# TPA3116D2.net
KiCad netlist of a schematic drawn in Altium Designer
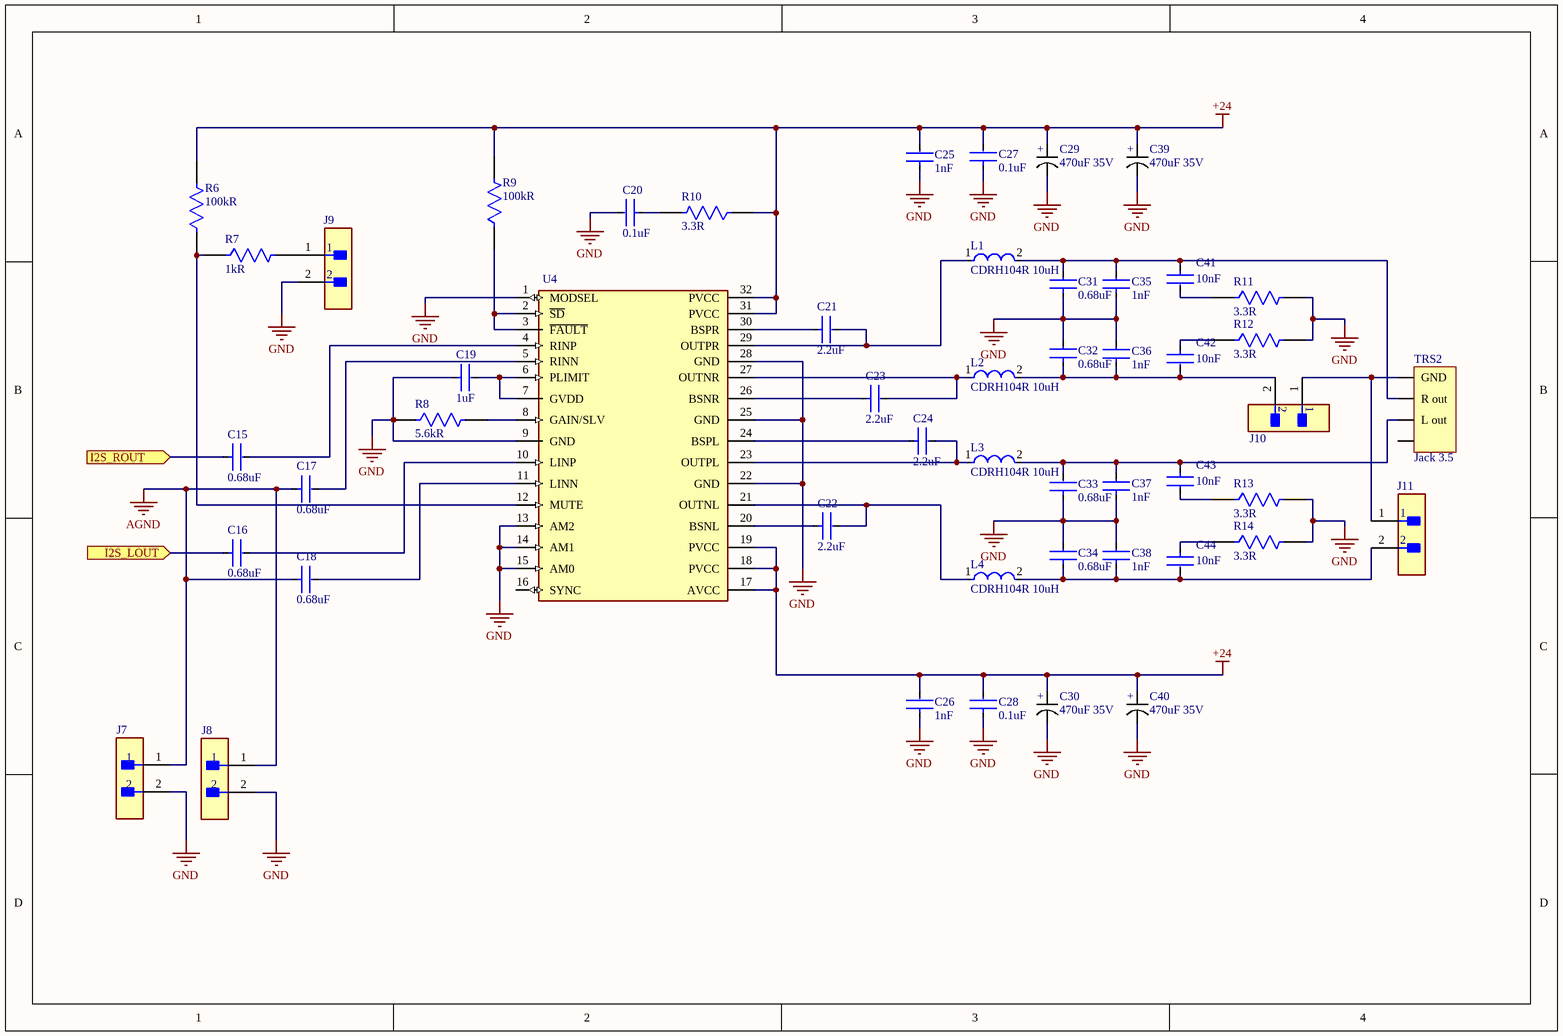
[diagram p0: TPA3116D2.SchDoc]

(export (version "E")
  (design (tool "Eeschema 10.0.6"))
  (components
    (comp (ref "C15")
      (value "0.68uF")
      (footprint "FP-CL21-IPC_C")
      (description "CL21 Series 0805 47nF 50V ±5% Tolerance X7R Multilayer Ceramic Chip Capacitor")
      (fields (field (name "TOLERANCE") "5%"))
      (libsource (lib "Altium Content Vault") (part "b4654b650e69147ec39a6b967a45e02"))
    )
    (comp (ref "C16")
      (value "0.68uF")
      (footprint "FP-CL21-IPC_C")
      (description "CL21 Series 0805 47nF 50V ±5% Tolerance X7R Multilayer Ceramic Chip Capacitor")
      (fields (field (name "TOLERANCE") "5%"))
      (libsource (lib "Altium Content Vault") (part "b4654b650e69147ec39a6b967a45e02"))
    )
    (comp (ref "C17")
      (value "0.68uF")
      (footprint "FP-CL21-IPC_C")
      (description "CL21 Series 0805 47nF 50V ±5% Tolerance X7R Multilayer Ceramic Chip Capacitor")
      (fields (field (name "TOLERANCE") "5%"))
      (libsource (lib "Altium Content Vault") (part "b4654b650e69147ec39a6b967a45e02"))
    )
    (comp (ref "C18")
      (value "0.68uF")
      (footprint "FP-CL21-IPC_C")
      (description "CL21 Series 0805 47nF 50V ±5% Tolerance X7R Multilayer Ceramic Chip Capacitor")
      (fields (field (name "TOLERANCE") "5%"))
      (libsource (lib "Altium Content Vault") (part "b4654b650e69147ec39a6b967a45e02"))
    )
    (comp (ref "C19")
      (value "1uF")
      (footprint "FP-CL21-IPC_C")
      (description "CL21 Series 0805 47nF 50V ±5% Tolerance X7R Multilayer Ceramic Chip Capacitor")
      (fields (field (name "TOLERANCE") "5%"))
      (libsource (lib "Altium Content Vault") (part "b4654b650e69147ec39a6b967a45e02"))
    )
    (comp (ref "C20")
      (value "0.1uF")
      (footprint "FP-CL21-IPC_C")
      (description "CL21 Series 0805 47nF 50V ±5% Tolerance X7R Multilayer Ceramic Chip Capacitor")
      (fields (field (name "TOLERANCE") "5%"))
      (libsource (lib "Altium Content Vault") (part "b4654b650e69147ec39a6b967a45e02"))
    )
    (comp (ref "C21")
      (value "2.2uF")
      (footprint "FP-CL21-IPC_C")
      (description "CL21 Series 0805 47nF 50V ±5% Tolerance X7R Multilayer Ceramic Chip Capacitor")
      (fields (field (name "TOLERANCE") "5%"))
      (libsource (lib "Altium Content Vault") (part "b4654b650e69147ec39a6b967a45e02"))
    )
    (comp (ref "C22")
      (value "2.2uF")
      (footprint "FP-CL21-IPC_C")
      (description "CL21 Series 0805 47nF 50V ±5% Tolerance X7R Multilayer Ceramic Chip Capacitor")
      (fields (field (name "TOLERANCE") "5%"))
      (libsource (lib "Altium Content Vault") (part "b4654b650e69147ec39a6b967a45e02"))
    )
    (comp (ref "C23")
      (value "2.2uF")
      (footprint "FP-CL21-IPC_C")
      (description "CL21 Series 0805 47nF 50V ±5% Tolerance X7R Multilayer Ceramic Chip Capacitor")
      (fields (field (name "TOLERANCE") "5%"))
      (libsource (lib "Altium Content Vault") (part "b4654b650e69147ec39a6b967a45e02"))
    )
    (comp (ref "C24")
      (value "2.2uF")
      (footprint "FP-CL21-IPC_C")
      (description "CL21 Series 0805 47nF 50V ±5% Tolerance X7R Multilayer Ceramic Chip Capacitor")
      (fields (field (name "TOLERANCE") "5%"))
      (libsource (lib "Altium Content Vault") (part "b4654b650e69147ec39a6b967a45e02"))
    )
    (comp (ref "C25")
      (value "1nF")
      (footprint "FP-CL21-IPC_C")
      (description "CL21 Series 0805 47nF 50V ±5% Tolerance X7R Multilayer Ceramic Chip Capacitor")
      (fields (field (name "TOLERANCE") "5%"))
      (libsource (lib "Altium Content Vault") (part "b4654b650e69147ec39a6b967a45e02"))
    )
    (comp (ref "C26")
      (value "1nF")
      (footprint "FP-CL21-IPC_C")
      (description "CL21 Series 0805 47nF 50V ±5% Tolerance X7R Multilayer Ceramic Chip Capacitor")
      (fields (field (name "TOLERANCE") "5%"))
      (libsource (lib "Altium Content Vault") (part "b4654b650e69147ec39a6b967a45e02"))
    )
    (comp (ref "C27")
      (value "0.1uF")
      (footprint "FP-CL21-IPC_C")
      (description "CL21 Series 0805 47nF 50V ±5% Tolerance X7R Multilayer Ceramic Chip Capacitor")
      (fields (field (name "TOLERANCE") "5%"))
      (libsource (lib "Altium Content Vault") (part "b4654b650e69147ec39a6b967a45e02"))
    )
    (comp (ref "C28")
      (value "0.1uF")
      (footprint "FP-CL21-IPC_C")
      (description "CL21 Series 0805 47nF 50V ±5% Tolerance X7R Multilayer Ceramic Chip Capacitor")
      (fields (field (name "TOLERANCE") "5%"))
      (libsource (lib "Altium Content Vault") (part "b4654b650e69147ec39a6b967a45e02"))
    )
    (comp (ref "C29")
      (value "470uF 35V")
      (footprint "CAP VT 470uF 35V")
      (libsource (lib "Schemati_design") (part "Cap{colon} VT 470uF 35V"))
    )
    (comp (ref "C30")
      (value "470uF 35V")
      (footprint "CAP VT 470uF 35V")
      (libsource (lib "Schemati_design") (part "Cap{colon} VT 470uF 35V"))
    )
    (comp (ref "C31")
      (value "0.68uF")
      (footprint "FP-CL21-IPC_C")
      (description "CL21 Series 0805 47nF 50V ±5% Tolerance X7R Multilayer Ceramic Chip Capacitor")
      (fields (field (name "TOLERANCE") "5%"))
      (libsource (lib "Altium Content Vault") (part "b4654b650e69147ec39a6b967a45e02"))
    )
    (comp (ref "C32")
      (value "0.68uF")
      (footprint "FP-CL21-IPC_C")
      (description "CL21 Series 0805 47nF 50V ±5% Tolerance X7R Multilayer Ceramic Chip Capacitor")
      (fields (field (name "TOLERANCE") "5%"))
      (libsource (lib "Altium Content Vault") (part "b4654b650e69147ec39a6b967a45e02"))
    )
    (comp (ref "C33")
      (value "0.68uF")
      (footprint "FP-CL21-IPC_C")
      (description "CL21 Series 0805 47nF 50V ±5% Tolerance X7R Multilayer Ceramic Chip Capacitor")
      (fields (field (name "TOLERANCE") "5%"))
      (libsource (lib "Altium Content Vault") (part "b4654b650e69147ec39a6b967a45e02"))
    )
    (comp (ref "C34")
      (value "0.68uF")
      (footprint "FP-CL21-IPC_C")
      (description "CL21 Series 0805 47nF 50V ±5% Tolerance X7R Multilayer Ceramic Chip Capacitor")
      (fields (field (name "TOLERANCE") "5%"))
      (libsource (lib "Altium Content Vault") (part "b4654b650e69147ec39a6b967a45e02"))
    )
    (comp (ref "C35")
      (value "1nF")
      (footprint "FP-CL21-IPC_C")
      (description "CL21 Series 0805 47nF 50V ±5% Tolerance X7R Multilayer Ceramic Chip Capacitor")
      (fields (field (name "TOLERANCE") "5%"))
      (libsource (lib "Altium Content Vault") (part "b4654b650e69147ec39a6b967a45e02"))
    )
    (comp (ref "C36")
      (value "1nF")
      (footprint "FP-CL21-IPC_C")
      (description "CL21 Series 0805 47nF 50V ±5% Tolerance X7R Multilayer Ceramic Chip Capacitor")
      (fields (field (name "TOLERANCE") "5%"))
      (libsource (lib "Altium Content Vault") (part "b4654b650e69147ec39a6b967a45e02"))
    )
    (comp (ref "C37")
      (value "1nF")
      (footprint "FP-CL21-IPC_C")
      (description "CL21 Series 0805 47nF 50V ±5% Tolerance X7R Multilayer Ceramic Chip Capacitor")
      (fields (field (name "TOLERANCE") "5%"))
      (libsource (lib "Altium Content Vault") (part "b4654b650e69147ec39a6b967a45e02"))
    )
    (comp (ref "C38")
      (value "1nF")
      (footprint "FP-CL21-IPC_C")
      (description "CL21 Series 0805 47nF 50V ±5% Tolerance X7R Multilayer Ceramic Chip Capacitor")
      (fields (field (name "TOLERANCE") "5%"))
      (libsource (lib "Altium Content Vault") (part "b4654b650e69147ec39a6b967a45e02"))
    )
    (comp (ref "C39")
      (value "470uF 35V")
      (footprint "CAP VT 470uF 35V")
      (libsource (lib "Schemati_design") (part "Cap{colon} VT 470uF 35V"))
    )
    (comp (ref "C40")
      (value "470uF 35V")
      (footprint "CAP VT 470uF 35V")
      (libsource (lib "Schemati_design") (part "Cap{colon} VT 470uF 35V"))
    )
    (comp (ref "C41")
      (value "10nF")
      (footprint "FP-CL21-IPC_C")
      (description "CL21 Series 0805 47nF 50V ±5% Tolerance X7R Multilayer Ceramic Chip Capacitor")
      (fields (field (name "TOLERANCE") "5%"))
      (libsource (lib "Altium Content Vault") (part "b4654b650e69147ec39a6b967a45e02"))
    )
    (comp (ref "C42")
      (value "10nF")
      (footprint "FP-CL21-IPC_C")
      (description "CL21 Series 0805 47nF 50V ±5% Tolerance X7R Multilayer Ceramic Chip Capacitor")
      (fields (field (name "TOLERANCE") "5%"))
      (libsource (lib "Altium Content Vault") (part "b4654b650e69147ec39a6b967a45e02"))
    )
    (comp (ref "C43")
      (value "10nF")
      (footprint "FP-CL21-IPC_C")
      (description "CL21 Series 0805 47nF 50V ±5% Tolerance X7R Multilayer Ceramic Chip Capacitor")
      (fields (field (name "TOLERANCE") "5%"))
      (libsource (lib "Altium Content Vault") (part "b4654b650e69147ec39a6b967a45e02"))
    )
    (comp (ref "C44")
      (value "10nF")
      (footprint "FP-CL21-IPC_C")
      (description "CL21 Series 0805 47nF 50V ±5% Tolerance X7R Multilayer Ceramic Chip Capacitor")
      (fields (field (name "TOLERANCE") "5%"))
      (libsource (lib "Altium Content Vault") (part "b4654b650e69147ec39a6b967a45e02"))
    )
    (comp (ref "J7")
      (value "M22-2510205")
      (footprint "FP-M22-2510205-MFG")
      (description "CONN HEADER VERT 2POS 2MM")
      (fields
        (field (name "MANUFACTURER") "Harwin")
        (field (name "OCTOPART") "https://octopart.com/m22-2510205-harwin-2538221")
      )
      (libsource (lib "Altium Content Vault") (part "3bc925449376181038e59eaffc5286c"))
    )
    (comp (ref "J8")
      (value "M22-2510205")
      (footprint "FP-M22-2510205-MFG")
      (description "CONN HEADER VERT 2POS 2MM")
      (fields
        (field (name "MANUFACTURER") "Harwin")
        (field (name "OCTOPART") "https://octopart.com/m22-2510205-harwin-2538221")
      )
      (libsource (lib "Altium Content Vault") (part "3bc925449376181038e59eaffc5286c"))
    )
    (comp (ref "J9")
      (value "M22-2510205")
      (footprint "FP-M22-2510205-MFG")
      (description "CONN HEADER VERT 2POS 2MM")
      (fields
        (field (name "MANUFACTURER") "Harwin")
        (field (name "OCTOPART") "https://octopart.com/m22-2510205-harwin-2538221")
      )
      (libsource (lib "") (part "3bc925449376181038e59eaffc5286c_1"))
    )
    (comp (ref "J10")
      (value "M22-2510205")
      (footprint "FP-M22-2510205-MFG")
      (description "CONN HEADER VERT 2POS 2MM")
      (fields
        (field (name "MANUFACTURER") "Harwin")
        (field (name "OCTOPART") "https://octopart.com/m22-2510205-harwin-2538221")
      )
      (libsource (lib "Altium Content Vault") (part "3bc925449376181038e59eaffc5286c"))
    )
    (comp (ref "J11")
      (value "M22-2510205")
      (footprint "FP-M22-2510205-MFG")
      (description "CONN HEADER VERT 2POS 2MM")
      (fields
        (field (name "MANUFACTURER") "Harwin")
        (field (name "OCTOPART") "https://octopart.com/m22-2510205-harwin-2538221")
      )
      (libsource (lib "") (part "3bc925449376181038e59eaffc5286c_1"))
    )
    (comp (ref "L1")
      (value "CDRH104R 10uH")
      (footprint "FP-CDRH104R-MFG")
      (description "FIXED IND 5.2UH 6A 22 MOHM SMD")
      (fields (field (name "TOLERANCE") "30%"))
      (libsource (lib "Altium Content Vault") (part "725321dda6339637d4d059423bc1c3c"))
    )
    (comp (ref "L2")
      (value "CDRH104R 10uH")
      (footprint "FP-CDRH104R-MFG")
      (description "FIXED IND 5.2UH 6A 22 MOHM SMD")
      (fields (field (name "TOLERANCE") "30%"))
      (libsource (lib "Altium Content Vault") (part "725321dda6339637d4d059423bc1c3c"))
    )
    (comp (ref "L3")
      (value "CDRH104R 10uH")
      (footprint "FP-CDRH104R-MFG")
      (description "FIXED IND 5.2UH 6A 22 MOHM SMD")
      (fields (field (name "TOLERANCE") "30%"))
      (libsource (lib "Altium Content Vault") (part "725321dda6339637d4d059423bc1c3c"))
    )
    (comp (ref "L4")
      (value "CDRH104R 10uH")
      (footprint "FP-CDRH104R-MFG")
      (description "FIXED IND 5.2UH 6A 22 MOHM SMD")
      (fields (field (name "TOLERANCE") "30%"))
      (libsource (lib "Altium Content Vault") (part "725321dda6339637d4d059423bc1c3c"))
    )
    (comp (ref "R6")
      (value "100kR")
      (footprint "FP-RP732A-IPC_C")
      (fields (field (name "TOLERANCE") "0.1%"))
      (libsource (lib "Altium Content Vault") (part "1029c3af85768c4190bb7ad29bc67b5"))
    )
    (comp (ref "R7")
      (value "1kR")
      (footprint "FP-RP732A-IPC_C")
      (fields (field (name "TOLERANCE") "0.1%"))
      (libsource (lib "Altium Content Vault") (part "1029c3af85768c4190bb7ad29bc67b5"))
    )
    (comp (ref "R8")
      (value "5.6kR")
      (footprint "FP-RP732A-IPC_C")
      (fields (field (name "TOLERANCE") "0.1%"))
      (libsource (lib "Altium Content Vault") (part "1029c3af85768c4190bb7ad29bc67b5"))
    )
    (comp (ref "R9")
      (value "100kR")
      (footprint "FP-RP732A-IPC_C")
      (fields (field (name "TOLERANCE") "0.1%"))
      (libsource (lib "Altium Content Vault") (part "1029c3af85768c4190bb7ad29bc67b5"))
    )
    (comp (ref "R10")
      (value "3.3R")
      (footprint "FP-RP732A-IPC_C")
      (fields (field (name "TOLERANCE") "0.1%"))
      (libsource (lib "Altium Content Vault") (part "1029c3af85768c4190bb7ad29bc67b5"))
    )
    (comp (ref "R11")
      (value "3.3R")
      (footprint "FP-RP732A-IPC_C")
      (fields (field (name "TOLERANCE") "0.1%"))
      (libsource (lib "Altium Content Vault") (part "1029c3af85768c4190bb7ad29bc67b5"))
    )
    (comp (ref "R12")
      (value "3.3R")
      (footprint "FP-RP732A-IPC_C")
      (fields (field (name "TOLERANCE") "0.1%"))
      (libsource (lib "Altium Content Vault") (part "1029c3af85768c4190bb7ad29bc67b5"))
    )
    (comp (ref "R13")
      (value "3.3R")
      (footprint "FP-RP732A-IPC_C")
      (fields (field (name "TOLERANCE") "0.1%"))
      (libsource (lib "Altium Content Vault") (part "1029c3af85768c4190bb7ad29bc67b5"))
    )
    (comp (ref "R14")
      (value "3.3R")
      (footprint "FP-RP732A-IPC_C")
      (fields (field (name "TOLERANCE") "0.1%"))
      (libsource (lib "Altium Content Vault") (part "1029c3af85768c4190bb7ad29bc67b5"))
    )
    (comp (ref "TRS2")
      (value "Jack 3.5")
      (footprint "PJ-327A")
      (libsource (lib "Schemati_design") (part "PJ327A"))
    )
    (comp (ref "U4")
      (value "TPA3116D2QDADRQ1")
      (footprint "FP-DAD0032C-MFG")
      (description "IC AMP CLASS D STER 50W 32HTSSOP")
      (libsource (lib "Altium Content Vault") (part "f73747c63f7b7a3aaa72a525ce68fc1"))
    )
  )
  (nets
    (net (code "1") (name "+24") (class "Default")
      (node (ref "C25") (pin "2") (pinfunction "2_2") (pintype "passive"))
      (node (ref "C26") (pin "2") (pinfunction "2_2") (pintype "passive"))
      (node (ref "C27") (pin "2") (pinfunction "2_2") (pintype "passive"))
      (node (ref "C28") (pin "2") (pinfunction "2_2") (pintype "passive"))
      (node (ref "C29") (pin "1") (pinfunction "+_1") (pintype "passive"))
      (node (ref "C30") (pin "1") (pinfunction "+_1") (pintype "passive"))
      (node (ref "C39") (pin "1") (pinfunction "+_1") (pintype "passive"))
      (node (ref "C40") (pin "1") (pinfunction "+_1") (pintype "passive"))
      (node (ref "R10") (pin "1") (pinfunction "1_1") (pintype "passive"))
      (node (ref "R6") (pin "2") (pinfunction "2_2") (pintype "passive"))
      (node (ref "R9") (pin "2") (pinfunction "2_2") (pintype "passive"))
      (node (ref "U4") (pin "17") (pinfunction "AVCC_17") (pintype "power_in"))
      (node (ref "U4") (pin "18") (pinfunction "PVCC_18") (pintype "power_in"))
      (node (ref "U4") (pin "19") (pinfunction "PVCC_19") (pintype "power_in"))
      (node (ref "U4") (pin "31") (pinfunction "PVCC_31") (pintype "power_in"))
      (node (ref "U4") (pin "32") (pinfunction "PVCC_32") (pintype "power_in"))
    )
    (net (code "2") (name "/I2S_LOUT") (class "Default")
      (node (ref "C16") (pin "1") (pinfunction "1_1") (pintype "passive"))
    )
    (net (code "3") (name "/I2S_ROUT") (class "Default")
      (node (ref "C15") (pin "1") (pinfunction "1_1") (pintype "passive"))
    )
    (net (code "4") (name "AGND") (class "Default")
      (node (ref "C17") (pin "1") (pinfunction "1_1") (pintype "passive"))
      (node (ref "C18") (pin "1") (pinfunction "1_1") (pintype "passive"))
      (node (ref "J7") (pin "1") (pinfunction "1_1") (pintype "passive"))
      (node (ref "J8") (pin "1") (pinfunction "1_1") (pintype "passive"))
    )
    (net (code "5") (name "GND") (class "Default")
      (node (ref "C19") (pin "1") (pinfunction "1_1") (pintype "passive"))
      (node (ref "C20") (pin "2") (pinfunction "2_2") (pintype "passive"))
      (node (ref "C25") (pin "1") (pinfunction "1_1") (pintype "passive"))
      (node (ref "C26") (pin "1") (pinfunction "1_1") (pintype "passive"))
      (node (ref "C27") (pin "1") (pinfunction "1_1") (pintype "passive"))
      (node (ref "C28") (pin "1") (pinfunction "1_1") (pintype "passive"))
      (node (ref "C29") (pin "2") (pinfunction "-_2") (pintype "passive"))
      (node (ref "C30") (pin "2") (pinfunction "-_2") (pintype "passive"))
      (node (ref "C31") (pin "1") (pinfunction "1_1") (pintype "passive"))
      (node (ref "C32") (pin "2") (pinfunction "2_2") (pintype "passive"))
      (node (ref "C33") (pin "1") (pinfunction "1_1") (pintype "passive"))
      (node (ref "C34") (pin "2") (pinfunction "2_2") (pintype "passive"))
      (node (ref "C35") (pin "1") (pinfunction "1_1") (pintype "passive"))
      (node (ref "C36") (pin "2") (pinfunction "2_2") (pintype "passive"))
      (node (ref "C37") (pin "1") (pinfunction "1_1") (pintype "passive"))
      (node (ref "C38") (pin "2") (pinfunction "2_2") (pintype "passive"))
      (node (ref "C39") (pin "2") (pinfunction "-_2") (pintype "passive"))
      (node (ref "C40") (pin "2") (pinfunction "-_2") (pintype "passive"))
      (node (ref "J7") (pin "2") (pinfunction "2_2") (pintype "passive"))
      (node (ref "J8") (pin "2") (pinfunction "2_2") (pintype "passive"))
      (node (ref "J9") (pin "2") (pinfunction "2_2") (pintype "passive"))
      (node (ref "R11") (pin "2") (pinfunction "2_2") (pintype "passive"))
      (node (ref "R12") (pin "2") (pinfunction "2_2") (pintype "passive"))
      (node (ref "R13") (pin "2") (pinfunction "2_2") (pintype "passive"))
      (node (ref "R14") (pin "2") (pinfunction "2_2") (pintype "passive"))
      (node (ref "R8") (pin "1") (pinfunction "1_1") (pintype "passive"))
      (node (ref "U4") (pin "1") (pinfunction "MODSEL_1") (pintype "bidirectional"))
      (node (ref "U4") (pin "13") (pinfunction "AM2_13") (pintype "input"))
      (node (ref "U4") (pin "14") (pinfunction "AM1_14") (pintype "input"))
      (node (ref "U4") (pin "15") (pinfunction "AM0_15") (pintype "input"))
      (node (ref "U4") (pin "22") (pinfunction "GND_22") (pintype "power_in"))
      (node (ref "U4") (pin "25") (pinfunction "GND_25") (pintype "power_in"))
      (node (ref "U4") (pin "28") (pinfunction "GND_28") (pintype "power_in"))
      (node (ref "U4") (pin "9") (pinfunction "GND_9") (pintype "power_in"))
    )
    (net (code "6") (name "Net-(C20-Pad1)") (class "Default")
      (node (ref "C20") (pin "1") (pinfunction "1_1") (pintype "passive"))
      (node (ref "R10") (pin "2") (pinfunction "2_2") (pintype "passive"))
    )
    (net (code "7") (name "Net-(C32-Pad1)") (class "Default")
      (node (ref "C32") (pin "1") (pinfunction "1_1") (pintype "passive"))
      (node (ref "C36") (pin "1") (pinfunction "1_1") (pintype "passive"))
      (node (ref "C42") (pin "2") (pinfunction "2_2") (pintype "passive"))
      (node (ref "J10") (pin "2") (pinfunction "2_2") (pintype "passive"))
      (node (ref "L2") (pin "2") (pinfunction "2_2") (pintype "passive"))
    )
    (net (code "8") (name "Net-(C34-Pad1)") (class "Default")
      (node (ref "C34") (pin "1") (pinfunction "1_1") (pintype "passive"))
      (node (ref "C38") (pin "1") (pinfunction "1_1") (pintype "passive"))
      (node (ref "C44") (pin "2") (pinfunction "2_2") (pintype "passive"))
      (node (ref "J11") (pin "2") (pinfunction "2_2") (pintype "passive"))
      (node (ref "L4") (pin "2") (pinfunction "2_2") (pintype "passive"))
    )
    (net (code "9") (name "Net-(C41-Pad2)") (class "Default")
      (node (ref "C41") (pin "2") (pinfunction "2_2") (pintype "passive"))
      (node (ref "R11") (pin "1") (pinfunction "1_1") (pintype "passive"))
    )
    (net (code "10") (name "Net-(C42-Pad1)") (class "Default")
      (node (ref "C42") (pin "1") (pinfunction "1_1") (pintype "passive"))
      (node (ref "R12") (pin "1") (pinfunction "1_1") (pintype "passive"))
    )
    (net (code "11") (name "Net-(C43-Pad2)") (class "Default")
      (node (ref "C43") (pin "2") (pinfunction "2_2") (pintype "passive"))
      (node (ref "R13") (pin "1") (pinfunction "1_1") (pintype "passive"))
    )
    (net (code "12") (name "Net-(C44-Pad1)") (class "Default")
      (node (ref "C44") (pin "1") (pinfunction "1_1") (pintype "passive"))
      (node (ref "R14") (pin "1") (pinfunction "1_1") (pintype "passive"))
    )
    (net (code "13") (name "Net-(J9-Pad1)") (class "Default")
      (node (ref "J9") (pin "1") (pinfunction "1_1") (pintype "passive"))
      (node (ref "R7") (pin "2") (pinfunction "2_2") (pintype "passive"))
    )
    (net (code "14") (name "Net-(TRS2-GND)") (class "Default")
      (node (ref "J10") (pin "1") (pinfunction "1_1") (pintype "passive"))
      (node (ref "J11") (pin "1") (pinfunction "1_1") (pintype "passive"))
      (node (ref "TRS2") (pin "1") (pinfunction "GND_1") (pintype "passive"))
    )
    (net (code "15") (name "Net-(TRS2-L_out)") (class "Default")
      (node (ref "C33") (pin "2") (pinfunction "2_2") (pintype "passive"))
      (node (ref "C37") (pin "2") (pinfunction "2_2") (pintype "passive"))
      (node (ref "C43") (pin "1") (pinfunction "1_1") (pintype "passive"))
      (node (ref "L3") (pin "2") (pinfunction "2_2") (pintype "passive"))
      (node (ref "TRS2") (pin "3") (pinfunction "L_out_3") (pintype "passive"))
    )
    (net (code "16") (name "Net-(TRS2-R_out)") (class "Default")
      (node (ref "C31") (pin "2") (pinfunction "2_2") (pintype "passive"))
      (node (ref "C35") (pin "2") (pinfunction "2_2") (pintype "passive"))
      (node (ref "C41") (pin "1") (pinfunction "1_1") (pintype "passive"))
      (node (ref "L1") (pin "2") (pinfunction "2_2") (pintype "passive"))
      (node (ref "TRS2") (pin "2") (pinfunction "R_out_2") (pintype "passive"))
    )
    (net (code "17") (name "Net-(U4-BSNL)") (class "Default")
      (node (ref "C22") (pin "1") (pinfunction "1_1") (pintype "passive"))
      (node (ref "U4") (pin "20") (pinfunction "BSNL_20") (pintype "passive"))
    )
    (net (code "18") (name "Net-(U4-BSNR)") (class "Default")
      (node (ref "C23") (pin "1") (pinfunction "1_1") (pintype "passive"))
      (node (ref "U4") (pin "26") (pinfunction "BSNR_26") (pintype "passive"))
    )
    (net (code "19") (name "Net-(U4-BSPL)") (class "Default")
      (node (ref "C24") (pin "1") (pinfunction "1_1") (pintype "passive"))
      (node (ref "U4") (pin "24") (pinfunction "BSPL_24") (pintype "passive"))
    )
    (net (code "20") (name "Net-(U4-BSPR)") (class "Default")
      (node (ref "C21") (pin "1") (pinfunction "1_1") (pintype "passive"))
      (node (ref "U4") (pin "30") (pinfunction "BSPR_30") (pintype "passive"))
    )
    (net (code "21") (name "Net-(U4-GAIN{slash}SLV)") (class "Default")
      (node (ref "R8") (pin "2") (pinfunction "2_2") (pintype "passive"))
      (node (ref "U4") (pin "8") (pinfunction "GAIN/SLV_8") (pintype "input"))
    )
    (net (code "22") (name "Net-(U4-GVDD)") (class "Default")
      (node (ref "C19") (pin "2") (pinfunction "2_2") (pintype "passive"))
      (node (ref "U4") (pin "6") (pinfunction "PLIMIT_6") (pintype "input"))
      (node (ref "U4") (pin "7") (pinfunction "GVDD_7") (pintype "power_in"))
    )
    (net (code "23") (name "Net-(U4-LINN)") (class "Default")
      (node (ref "C18") (pin "2") (pinfunction "2_2") (pintype "passive"))
      (node (ref "U4") (pin "11") (pinfunction "LINN_11") (pintype "input"))
    )
    (net (code "24") (name "Net-(U4-LINP)") (class "Default")
      (node (ref "C16") (pin "2") (pinfunction "2_2") (pintype "passive"))
      (node (ref "U4") (pin "10") (pinfunction "LINP_10") (pintype "input"))
    )
    (net (code "25") (name "Net-(U4-MUTE)") (class "Default")
      (node (ref "R6") (pin "1") (pinfunction "1_1") (pintype "passive"))
      (node (ref "R7") (pin "1") (pinfunction "1_1") (pintype "passive"))
      (node (ref "U4") (pin "12") (pinfunction "MUTE_12") (pintype "input"))
    )
    (net (code "26") (name "Net-(U4-OUTNL)") (class "Default")
      (node (ref "C22") (pin "2") (pinfunction "2_2") (pintype "passive"))
      (node (ref "L4") (pin "1") (pinfunction "1_1") (pintype "passive"))
      (node (ref "U4") (pin "21") (pinfunction "OUTNL_21") (pintype "passive"))
    )
    (net (code "27") (name "Net-(U4-OUTNR)") (class "Default")
      (node (ref "C23") (pin "2") (pinfunction "2_2") (pintype "passive"))
      (node (ref "L2") (pin "1") (pinfunction "1_1") (pintype "passive"))
      (node (ref "U4") (pin "27") (pinfunction "OUTNR_27") (pintype "passive"))
    )
    (net (code "28") (name "Net-(U4-OUTPL)") (class "Default")
      (node (ref "C24") (pin "2") (pinfunction "2_2") (pintype "passive"))
      (node (ref "L3") (pin "1") (pinfunction "1_1") (pintype "passive"))
      (node (ref "U4") (pin "23") (pinfunction "OUTPL_23") (pintype "passive"))
    )
    (net (code "29") (name "Net-(U4-OUTPR)") (class "Default")
      (node (ref "C21") (pin "2") (pinfunction "2_2") (pintype "passive"))
      (node (ref "L1") (pin "1") (pinfunction "1_1") (pintype "passive"))
      (node (ref "U4") (pin "29") (pinfunction "OUTPR_29") (pintype "passive"))
    )
    (net (code "30") (name "Net-(U4-RINN)") (class "Default")
      (node (ref "C17") (pin "2") (pinfunction "2_2") (pintype "passive"))
      (node (ref "U4") (pin "5") (pinfunction "RINN_5") (pintype "input"))
    )
    (net (code "31") (name "Net-(U4-RINP)") (class "Default")
      (node (ref "C15") (pin "2") (pinfunction "2_2") (pintype "passive"))
      (node (ref "U4") (pin "4") (pinfunction "RINP_4") (pintype "input"))
    )
    (net (code "32") (name "Net-(U4-~{FAULT})") (class "Default")
      (node (ref "R9") (pin "1") (pinfunction "1_1") (pintype "passive"))
      (node (ref "U4") (pin "2") (pinfunction "~{SD}_2") (pintype "input"))
      (node (ref "U4") (pin "3") (pinfunction "~{FAULT}_3") (pintype "open_collector"))
    )
    (net (code "33") (name "unconnected-(TRS2-Pad4)") (class "Default")
      (node (ref "TRS2") (pin "4") (pinfunction "4_4") (pintype "passive"))
    )
    (net (code "34") (name "unconnected-(U4-SYNC-Pad16)") (class "Default")
      (node (ref "U4") (pin "16") (pinfunction "SYNC_16") (pintype "bidirectional"))
    )
  )
)
